# VestibularVR_H1-module_v_1_1.net
KiCad netlist of a schematic drawn in EAGLE
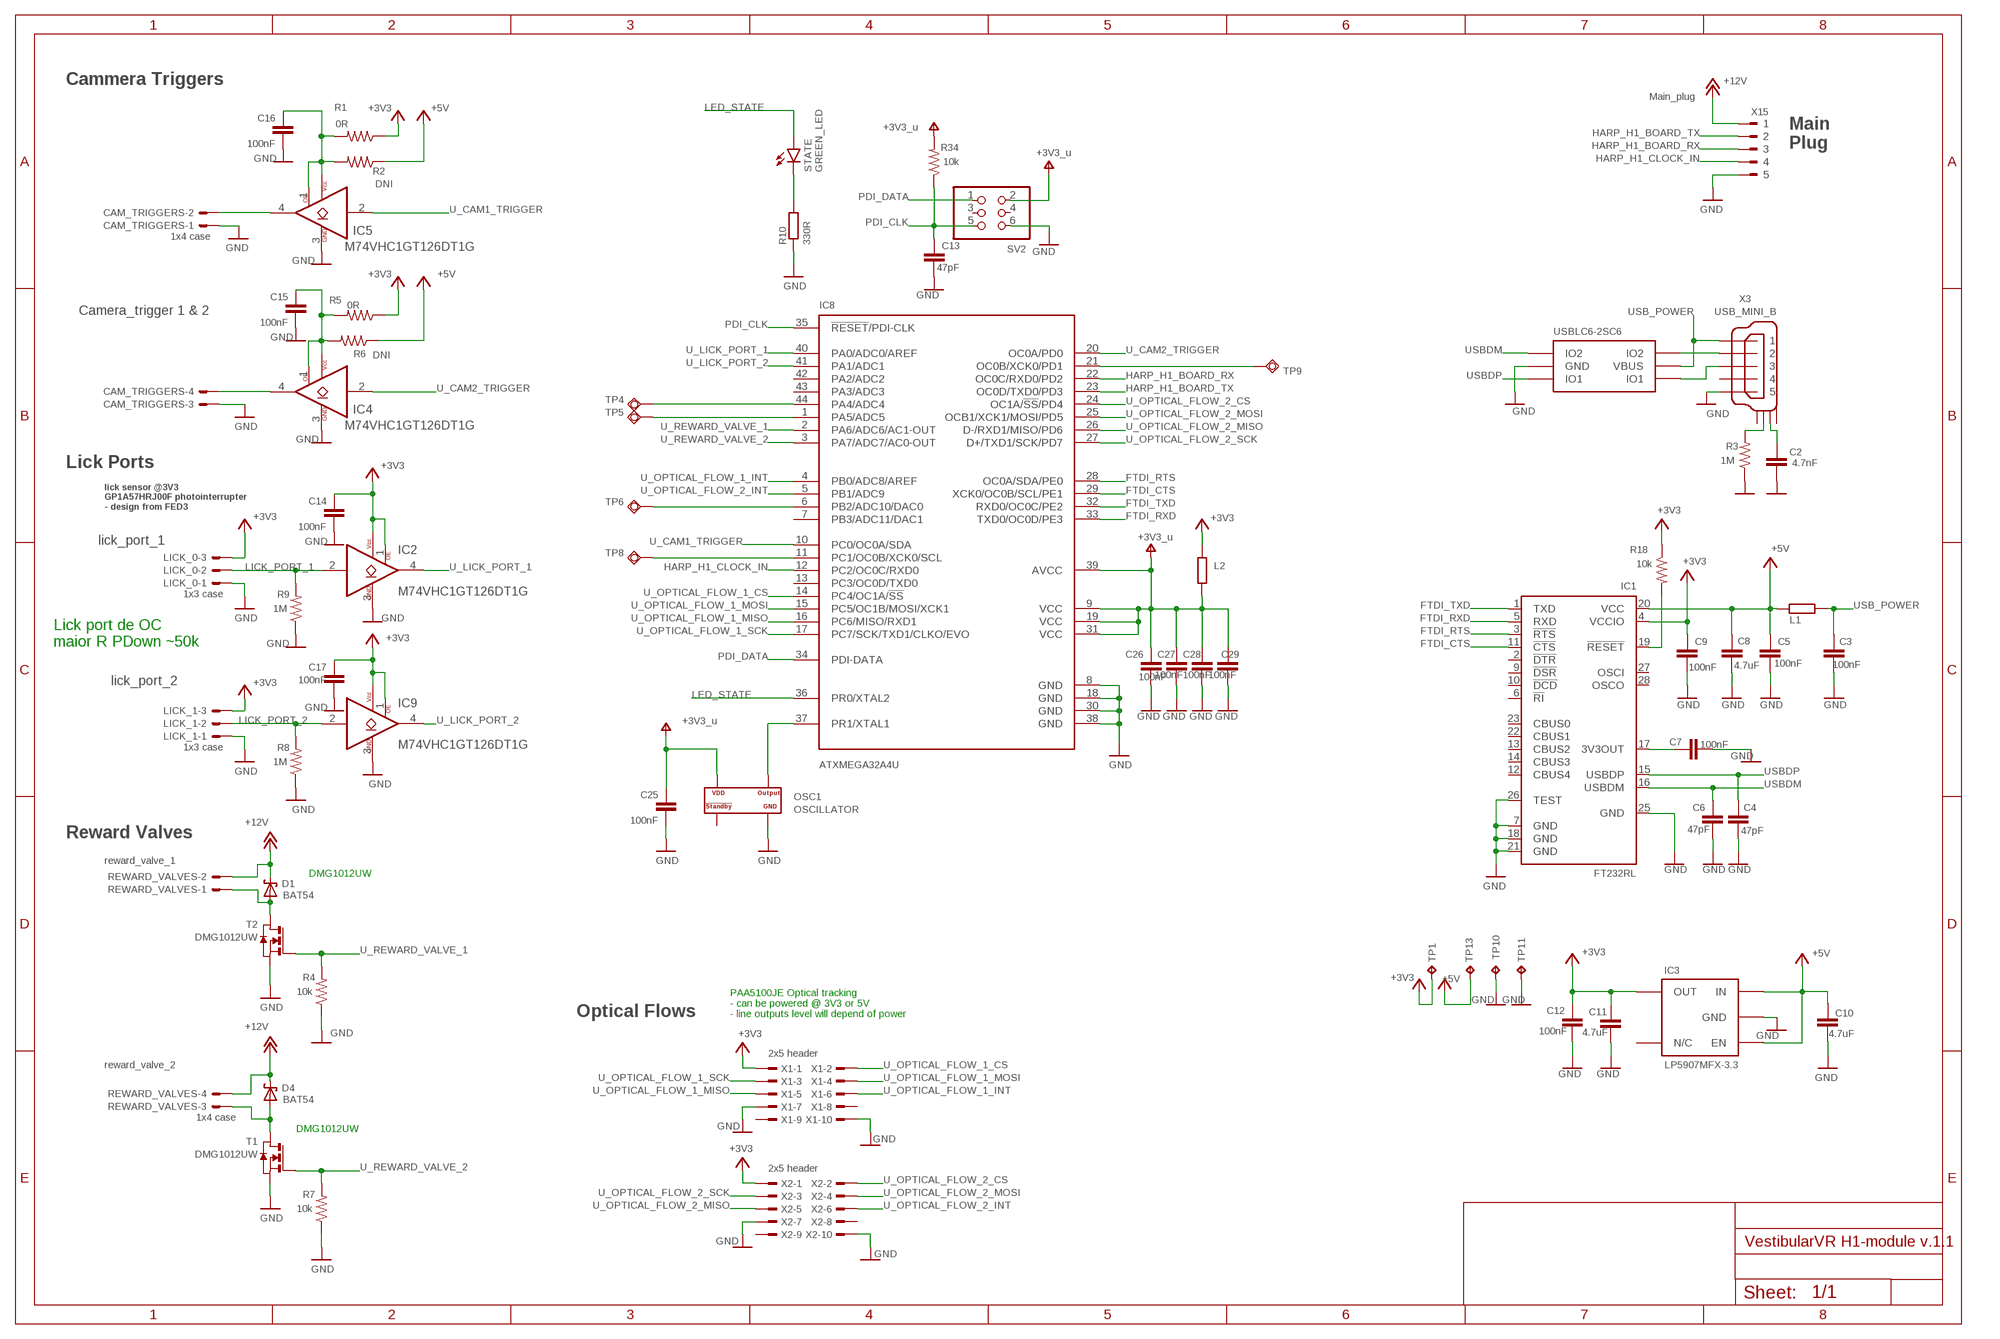
[diagram p0: schematic, sheet 1]

(export (version "E")
  (design (tool "Eeschema 10.0.6"))
  (components
    (comp (ref "C2")
      (value "4.7nF")
      (footprint "eagle-import:C0402K")
      (fields (field (name "MPN") "CC0402KRX7R8BB472"))
      (libsource (lib "eagle-import") (part "C-EUC0402K"))
    )
    (comp (ref "C3")
      (value "100nF")
      (footprint "eagle-import:C0402K")
      (fields (field (name "MPN") "C1005X7R1H104K050BB"))
      (libsource (lib "eagle-import") (part "C-EUC0402K"))
    )
    (comp (ref "C4")
      (value "47pF")
      (footprint "eagle-import:C0402K")
      (fields (field (name "MPN") "04025A470JAT2A"))
      (libsource (lib "eagle-import") (part "C-EUC0402K"))
    )
    (comp (ref "C5")
      (value "100nF")
      (footprint "eagle-import:C0402K")
      (fields (field (name "MPN") "C1005X7R1H104K050BB"))
      (libsource (lib "eagle-import") (part "C-EUC0402K"))
    )
    (comp (ref "C6")
      (value "47pF")
      (footprint "eagle-import:C0402K")
      (fields (field (name "MPN") "04025A470JAT2A"))
      (libsource (lib "eagle-import") (part "C-EUC0402K"))
    )
    (comp (ref "C7")
      (value "100nF")
      (footprint "eagle-import:C0402K")
      (fields (field (name "MPN") "C1005X7R1H104K050BB"))
      (libsource (lib "eagle-import") (part "C-EUC0402K"))
    )
    (comp (ref "C8")
      (value "4.7uF")
      (footprint "eagle-import:C0603")
      (fields (field (name "MPN") "C1608X6S1C475K080AC"))
      (libsource (lib "eagle-import") (part "C-EUC0603"))
    )
    (comp (ref "C9")
      (value "100nF")
      (footprint "eagle-import:C0402K")
      (fields (field (name "MPN") "C1005X7R1H104K050BB"))
      (libsource (lib "eagle-import") (part "C-EUC0402K"))
    )
    (comp (ref "C10")
      (value "4.7uF")
      (footprint "eagle-import:C0603K")
      (fields (field (name "MPN") "C1608X6S1C475K080AC"))
      (libsource (lib "eagle-import") (part "C-EUC0603K"))
    )
    (comp (ref "C11")
      (value "4.7uF")
      (footprint "eagle-import:C0603K")
      (fields (field (name "MPN") "C1608X6S1C475K080AC"))
      (libsource (lib "eagle-import") (part "C-EUC0603K"))
    )
    (comp (ref "C12")
      (value "100nF")
      (footprint "eagle-import:C0402K")
      (fields (field (name "MPN") "C1005X7R1H104K050BB"))
      (libsource (lib "eagle-import") (part "C-EUC0402K"))
    )
    (comp (ref "C13")
      (value "47pF")
      (footprint "eagle-import:C0402K")
      (fields (field (name "MPN") "04025A470JAT2A"))
      (libsource (lib "eagle-import") (part "C-EUC0402K"))
    )
    (comp (ref "C14")
      (value "100nF")
      (footprint "eagle-import:C0402K")
      (fields (field (name "MPN") "C1005X7R1H104K050BB"))
      (libsource (lib "eagle-import") (part "C-EUC0402K"))
    )
    (comp (ref "C15")
      (value "100nF")
      (footprint "eagle-import:C0402K")
      (fields (field (name "MPN") "C1005X7R1H104K050BB"))
      (libsource (lib "eagle-import") (part "C-EUC0402K"))
    )
    (comp (ref "C16")
      (value "100nF")
      (footprint "eagle-import:C0402K")
      (fields (field (name "MPN") "C1005X7R1H104K050BB"))
      (libsource (lib "eagle-import") (part "C-EUC0402K"))
    )
    (comp (ref "C17")
      (value "100nF")
      (footprint "eagle-import:C0402K")
      (fields (field (name "MPN") "C1005X7R1H104K050BB"))
      (libsource (lib "eagle-import") (part "C-EUC0402K"))
    )
    (comp (ref "C25")
      (value "100nF")
      (footprint "eagle-import:C0402K")
      (fields (field (name "MPN") "C1005X7R1H104K050BB"))
      (libsource (lib "eagle-import") (part "C-EUC0402K"))
    )
    (comp (ref "C26")
      (value "100nF")
      (footprint "eagle-import:C0402K")
      (fields (field (name "MPN") "C1005X7R1H104K050BB"))
      (libsource (lib "eagle-import") (part "C-EUC0402K"))
    )
    (comp (ref "C27")
      (value "100nF")
      (footprint "eagle-import:C0402K")
      (fields (field (name "MPN") "C1005X7R1H104K050BB"))
      (libsource (lib "eagle-import") (part "C-EUC0402K"))
    )
    (comp (ref "C28")
      (value "100nF")
      (footprint "eagle-import:C0402K")
      (fields (field (name "MPN") "C1005X7R1H104K050BB"))
      (libsource (lib "eagle-import") (part "C-EUC0402K"))
    )
    (comp (ref "C29")
      (value "100nF")
      (footprint "eagle-import:C0402K")
      (fields (field (name "MPN") "C1005X7R1H104K050BB"))
      (libsource (lib "eagle-import") (part "C-EUC0402K"))
    )
    (comp (ref "CAM_TRIGGERS")
      (value "1x4 case")
      (footprint "eagle-import:22-23-2041")
      (fields
        (field (name "MF") "MOLEX")
        (field (name "MPN") "22-23-2041")
        (field (name "MF_1") "-")
        (field (name "MPN_1") "282834-4")
        (field (name "OEPS") "OEPS070036")
      )
      (libsource (lib "eagle-import") (part "22-23-2041"))
    )
    (comp (ref "D1")
      (value "BAT54")
      (footprint "eagle-import:SOT23")
      (fields (field (name "MPN") "BAT54SLT1G"))
      (libsource (lib "eagle-import") (part "BAT54"))
    )
    (comp (ref "D4")
      (value "BAT54")
      (footprint "eagle-import:SOT23")
      (fields (field (name "MPN") "BAT54SLT1G"))
      (libsource (lib "eagle-import") (part "BAT54"))
    )
    (comp (ref "IC1")
      (value "FT232RL")
      (footprint "eagle-import:SSOP28")
      (libsource (lib "eagle-import") (part "FT232RL"))
    )
    (comp (ref "IC2")
      (value "M74VHC1GT126DT1G")
      (footprint "eagle-import:TSOP-5")
      (libsource (lib "eagle-import") (part "M74VHC1GT126DT1G"))
    )
    (comp (ref "IC3")
      (value "LP5907MFX-3.3")
      (footprint "eagle-import:TSOT23-5")
      (fields (field (name "MPN") "LP5907MFX-3.3/NOPB"))
      (libsource (lib "eagle-import") (part "TLV700XX"))
    )
    (comp (ref "IC4")
      (value "M74VHC1GT126DT1G")
      (footprint "eagle-import:TSOP-5")
      (libsource (lib "eagle-import") (part "M74VHC1GT126DT1G"))
    )
    (comp (ref "IC5")
      (value "M74VHC1GT126DT1G")
      (footprint "eagle-import:TSOP-5")
      (libsource (lib "eagle-import") (part "M74VHC1GT126DT1G"))
    )
    (comp (ref "IC7")
      (value "USBLC6-2SC6")
      (footprint "eagle-import:SOT23-6L")
      (libsource (lib "eagle-import") (part "USBLC6-2SC6"))
    )
    (comp (ref "IC8")
      (value "ATXMEGA32A4U")
      (footprint "eagle-import:TQFP44")
      (fields (field (name "MPN") "ATXMEGA32A4U-AUR"))
      (libsource (lib "eagle-import") (part "XMEGA-A4_AT-XMEGA-XXA4-AUTQFP44"))
    )
    (comp (ref "IC9")
      (value "M74VHC1GT126DT1G")
      (footprint "eagle-import:TSOP-5")
      (libsource (lib "eagle-import") (part "M74VHC1GT126DT1G"))
    )
    (comp (ref "L1")
      (value "40R@100MHz")
      (footprint "eagle-import:R0603")
      (fields (field (name "MPN") "MI0805K400R-10"))
      (libsource (lib "eagle-import") (part "R-EU_R0603"))
    )
    (comp (ref "L2")
      (value "40R@100MHz")
      (footprint "eagle-import:R0603")
      (fields (field (name "MPN") "MI0805K400R-10"))
      (libsource (lib "eagle-import") (part "R-EU_R0603"))
    )
    (comp (ref "LICK_0")
      (value "1x3 case")
      (footprint "eagle-import:22-23-2031")
      (fields
        (field (name "MF") "MOLEX")
        (field (name "MPN") "22-23-2031")
        (field (name "MF_1") "-")
        (field (name "MPN_1") "282834-3")
        (field (name "OEPS") "OEPS070035")
      )
      (libsource (lib "eagle-import") (part "22-23-2031"))
    )
    (comp (ref "LICK_1")
      (value "1x3 case")
      (footprint "eagle-import:22-23-2031")
      (fields
        (field (name "MF") "MOLEX")
        (field (name "MPN") "22-23-2031")
        (field (name "MF_1") "-")
        (field (name "MPN_1") "282834-3")
        (field (name "OEPS") "OEPS070035")
      )
      (libsource (lib "eagle-import") (part "22-23-2031"))
    )
    (comp (ref "OSC1")
      (value "OSCILLATOR")
      (footprint "eagle-import:OSCILLATOR_3.2X2.5")
      (fields (field (name "MPN") "DSC1001CI5-032.0000"))
      (libsource (lib "eagle-import") (part "OSCILLATOR"))
    )
    (comp (ref "R1")
      (value "0R")
      (footprint "eagle-import:R0402@1")
      (fields (field (name "MPN") "RC0402JR-070RL"))
      (libsource (lib "eagle-import") (part "R-US_R0402"))
    )
    (comp (ref "R2")
      (value "DNI")
      (footprint "eagle-import:R0402@1")
      (libsource (lib "eagle-import") (part "R-US_R0402"))
    )
    (comp (ref "R3")
      (value "1M")
      (footprint "eagle-import:R0402@1")
      (fields (field (name "MPN") "CRCW04021M00FKED"))
      (libsource (lib "eagle-import") (part "R-US_R0402"))
    )
    (comp (ref "R4")
      (value "10k")
      (footprint "eagle-import:R0402@1")
      (fields (field (name "MPN") "CRCW040210K0FKED"))
      (libsource (lib "eagle-import") (part "R-US_R0402"))
    )
    (comp (ref "R5")
      (value "0R")
      (footprint "eagle-import:R0402@1")
      (fields (field (name "MPN") "RC0402JR-070RL"))
      (libsource (lib "eagle-import") (part "R-US_R0402"))
    )
    (comp (ref "R6")
      (value "DNI")
      (footprint "eagle-import:R0402@1")
      (libsource (lib "eagle-import") (part "R-US_R0402"))
    )
    (comp (ref "R7")
      (value "10k")
      (footprint "eagle-import:R0402@1")
      (fields (field (name "MPN") "CRCW040210K0FKED"))
      (libsource (lib "eagle-import") (part "R-US_R0402"))
    )
    (comp (ref "R8")
      (value "1M")
      (footprint "eagle-import:R0402@1")
      (fields (field (name "MPN") "CRCW04021M00FKED"))
      (libsource (lib "eagle-import") (part "R-US_R0402"))
    )
    (comp (ref "R9")
      (value "1M")
      (footprint "eagle-import:R0402@1")
      (fields (field (name "MPN") "CRCW04021M00FKED"))
      (libsource (lib "eagle-import") (part "R-US_R0402"))
    )
    (comp (ref "R10")
      (value "330R")
      (footprint "eagle-import:R0402")
      (fields (field (name "MPN") "RC0402FR-07330RL"))
      (libsource (lib "eagle-import") (part "R-EU_R0402"))
    )
    (comp (ref "R18")
      (value "10k")
      (footprint "eagle-import:R0402@1")
      (fields (field (name "MPN") "CRCW040210K0FKED"))
      (libsource (lib "eagle-import") (part "R-US_R0402"))
    )
    (comp (ref "R34")
      (value "10k")
      (footprint "eagle-import:R0402@1")
      (fields (field (name "MPN") "CRCW040210K0FKED"))
      (libsource (lib "eagle-import") (part "R-US_R0402"))
    )
    (comp (ref "REWARD_VALVES")
      (value "1x4 case")
      (footprint "eagle-import:22-23-2041")
      (fields
        (field (name "MF") "MOLEX")
        (field (name "MPN") "22-23-2041")
        (field (name "MF_1") "-")
        (field (name "MPN_1") "282834-4")
        (field (name "OEPS") "OEPS070036")
      )
      (libsource (lib "eagle-import") (part "22-23-2041"))
    )
    (comp (ref "STATE")
      (value "GREEN_LED")
      (footprint "eagle-import:CHIP-LED0603")
      (fields (field (name "MPN") "LTST-C191KGKT"))
      (libsource (lib "eagle-import") (part "LEDCHIP-LED0603"))
    )
    (comp (ref "SV2")
      (value "PINHD-2X3")
      (footprint "eagle-import:2X03")
      (fields (field (name "MPN") "609-3210-ND"))
      (libsource (lib "eagle-import") (part "PINHD-2X3"))
    )
    (comp (ref "T1")
      (value "DMG1012UW")
      (footprint "eagle-import:SOT323")
      (fields (field (name "MPN") "DMG1012UW-7"))
      (libsource (lib "eagle-import") (part "DMG1012UW-7"))
    )
    (comp (ref "T2")
      (value "DMG1012UW")
      (footprint "eagle-import:SOT323")
      (fields (field (name "MPN") "DMG1012UW-7"))
      (libsource (lib "eagle-import") (part "DMG1012UW-7"))
    )
    (comp (ref "TP1")
      (value "NO_COMPONENT")
      (footprint "eagle-import:B1,27")
      (libsource (lib "eagle-import") (part "TPB1,27"))
    )
    (comp (ref "TP4")
      (value "NO_COMPONENT")
      (footprint "eagle-import:TP11R")
      (libsource (lib "eagle-import") (part "TPSQTP11R"))
    )
    (comp (ref "TP5")
      (value "NO_COMPONENT")
      (footprint "eagle-import:TP11R")
      (libsource (lib "eagle-import") (part "TPSQTP11R"))
    )
    (comp (ref "TP6")
      (value "NO_COMPONENT")
      (footprint "eagle-import:TP11R")
      (libsource (lib "eagle-import") (part "TPSQTP11R"))
    )
    (comp (ref "TP8")
      (value "NO_COMPONENT")
      (footprint "eagle-import:TP11R")
      (libsource (lib "eagle-import") (part "TPSQTP11R"))
    )
    (comp (ref "TP9")
      (value "NO_COMPONENT")
      (footprint "eagle-import:TP11R")
      (libsource (lib "eagle-import") (part "TPSQTP11R"))
    )
    (comp (ref "TP10")
      (value "NO_COMPONENT")
      (footprint "eagle-import:B1,27")
      (libsource (lib "eagle-import") (part "TPB1,27"))
    )
    (comp (ref "TP11")
      (value "NO_COMPONENT")
      (footprint "eagle-import:B1,27")
      (libsource (lib "eagle-import") (part "TPB1,27"))
    )
    (comp (ref "TP13")
      (value "NO_COMPONENT")
      (footprint "eagle-import:B1,27")
      (libsource (lib "eagle-import") (part "TPB1,27"))
    )
    (comp (ref "X1")
      (value "2x5 header")
      (footprint "eagle-import:TSW-105-02-S-D")
      (fields (field (name "MPN") "2x5 header") (field (name "OEPS") "n.a."))
      (libsource (lib "eagle-import") (part "TSW-105-02-S-D"))
    )
    (comp (ref "X2")
      (value "2x5 header")
      (footprint "eagle-import:TSW-105-02-S-D")
      (fields (field (name "MPN") "2x5 header") (field (name "OEPS") "n.a."))
      (libsource (lib "eagle-import") (part "TSW-105-02-S-D"))
    )
    (comp (ref "X3")
      (value "USB_MINI_B")
      (footprint "eagle-import:240-0002-1")
      (fields (field (name "MPN") "UX60-MB-5S8"))
      (libsource (lib "eagle-import") (part "USB_MINI_B"))
    )
    (comp (ref "X15")
      (value "Main_plug")
      (footprint "eagle-import:90G-5")
      (fields (field (name "MPN") "20.155MH/5-E"))
      (libsource (lib "eagle-import") (part "90G-5"))
    )
  )
  (nets
    (net (code "1") (name "+3V3") (class "Default")
      (node (ref "C11") (pin "1") (pinfunction "1_1") (pintype "passive"))
      (node (ref "C12") (pin "1") (pinfunction "1_1") (pintype "passive"))
      (node (ref "C14") (pin "1") (pinfunction "1_1") (pintype "passive"))
      (node (ref "C17") (pin "1") (pinfunction "1_1") (pintype "passive"))
      (node (ref "C9") (pin "1") (pinfunction "1_1") (pintype "passive"))
      (node (ref "IC1") (pin "4") (pinfunction "VCCIO_4") (pintype "power_in"))
      (node (ref "IC2") (pin "1") (pinfunction "OE_1") (pintype "bidirectional"))
      (node (ref "IC2") (pin "5") (pinfunction "VCC_5") (pintype "bidirectional"))
      (node (ref "IC3") (pin "5") (pinfunction "OUT_5") (pintype "bidirectional"))
      (node (ref "IC9") (pin "1") (pinfunction "OE_1") (pintype "bidirectional"))
      (node (ref "IC9") (pin "5") (pinfunction "VCC_5") (pintype "bidirectional"))
      (node (ref "L2") (pin "2") (pinfunction "2_2") (pintype "passive"))
      (node (ref "LICK_0") (pin "3") (pinfunction "S_3") (pintype "passive"))
      (node (ref "LICK_1") (pin "3") (pinfunction "S_3") (pintype "passive"))
      (node (ref "R1") (pin "1") (pinfunction "1_1") (pintype "passive"))
      (node (ref "R18") (pin "1") (pinfunction "1_1") (pintype "passive"))
      (node (ref "R5") (pin "1") (pinfunction "1_1") (pintype "passive"))
      (node (ref "TP1") (pin "TP") (pinfunction "TP_TP") (pintype "input"))
      (node (ref "X1") (pin "1") (pinfunction "1_1") (pintype "passive"))
      (node (ref "X2") (pin "1") (pinfunction "1_1") (pintype "passive"))
    )
    (net (code "2") (name "+3V3_u") (class "Default")
      (node (ref "C25") (pin "1") (pinfunction "1_1") (pintype "passive"))
      (node (ref "C26") (pin "1") (pinfunction "1_1") (pintype "passive"))
      (node (ref "C27") (pin "1") (pinfunction "1_1") (pintype "passive"))
      (node (ref "C28") (pin "1") (pinfunction "1_1") (pintype "passive"))
      (node (ref "C29") (pin "1") (pinfunction "1_1") (pintype "passive"))
      (node (ref "IC8") (pin "19") (pinfunction "VCC_19") (pintype "power_in"))
      (node (ref "IC8") (pin "31") (pinfunction "VCC_31") (pintype "power_in"))
      (node (ref "IC8") (pin "39") (pinfunction "AVCC_39") (pintype "power_in"))
      (node (ref "IC8") (pin "9") (pinfunction "VCC_9") (pintype "power_in"))
      (node (ref "L2") (pin "1") (pinfunction "1_1") (pintype "passive"))
      (node (ref "OSC1") (pin "P$4") (pinfunction "VDD_P$4") (pintype "passive"))
      (node (ref "R34") (pin "2") (pinfunction "2_2") (pintype "passive"))
      (node (ref "SV2") (pin "2") (pinfunction "2_2") (pintype "passive"))
    )
    (net (code "3") (name "+5V") (class "Default")
      (node (ref "C10") (pin "1") (pinfunction "1_1") (pintype "passive"))
      (node (ref "C5") (pin "1") (pinfunction "1_1") (pintype "passive"))
      (node (ref "C8") (pin "1") (pinfunction "1_1") (pintype "passive"))
      (node (ref "IC1") (pin "20") (pinfunction "VCC_20") (pintype "power_in"))
      (node (ref "IC3") (pin "1") (pinfunction "IN_1") (pintype "bidirectional"))
      (node (ref "IC3") (pin "3") (pinfunction "EN_3") (pintype "bidirectional"))
      (node (ref "L1") (pin "1") (pinfunction "1_1") (pintype "passive"))
      (node (ref "R2") (pin "1") (pinfunction "1_1") (pintype "passive"))
      (node (ref "R6") (pin "1") (pinfunction "1_1") (pintype "passive"))
      (node (ref "TP13") (pin "TP") (pinfunction "TP_TP") (pintype "input"))
    )
    (net (code "4") (name "+12V") (class "Default")
      (node (ref "D1") (pin "3") (pinfunction "C_3") (pintype "passive"))
      (node (ref "D4") (pin "3") (pinfunction "C_3") (pintype "passive"))
      (node (ref "REWARD_VALVES") (pin "2") (pinfunction "S_2") (pintype "passive"))
      (node (ref "REWARD_VALVES") (pin "4") (pinfunction "S_4") (pintype "passive"))
      (node (ref "X15") (pin "1") (pinfunction "1_1") (pintype "passive"))
    )
    (net (code "5") (name "/FTDI_CTS") (class "Default")
      (node (ref "IC1") (pin "11") (pinfunction "~{CTS}_11") (pintype "input"))
      (node (ref "IC8") (pin "29") (pinfunction "XCK0/OC0B/SCL/PE1_29") (pintype "bidirectional"))
    )
    (net (code "6") (name "/FTDI_RTS") (class "Default")
      (node (ref "IC1") (pin "3") (pinfunction "~{RTS}_3") (pintype "output"))
      (node (ref "IC8") (pin "28") (pinfunction "OC0A/SDA/PE0_28") (pintype "bidirectional"))
    )
    (net (code "7") (name "/FTDI_RXD") (class "Default")
      (node (ref "IC1") (pin "5") (pinfunction "RXD_5") (pintype "input"))
      (node (ref "IC8") (pin "33") (pinfunction "TXD0/OC0D/PE3_33") (pintype "bidirectional"))
    )
    (net (code "8") (name "/FTDI_TXD") (class "Default")
      (node (ref "IC1") (pin "1") (pinfunction "TXD_1") (pintype "output"))
      (node (ref "IC8") (pin "32") (pinfunction "RXD0/OC0C/PE2_32") (pintype "bidirectional"))
    )
    (net (code "9") (name "/HARP_H1_BOARD_RX") (class "Default")
      (node (ref "IC8") (pin "22") (pinfunction "OC0C/RXD0/PD2_22") (pintype "bidirectional"))
      (node (ref "X15") (pin "3") (pinfunction "3_3") (pintype "passive"))
    )
    (net (code "10") (name "/HARP_H1_BOARD_TX") (class "Default")
      (node (ref "IC8") (pin "23") (pinfunction "OC0D/TXD0/PD3_23") (pintype "bidirectional"))
      (node (ref "X15") (pin "2") (pinfunction "2_2") (pintype "passive"))
    )
    (net (code "11") (name "/HARP_H1_CLOCK_IN") (class "Default")
      (node (ref "IC8") (pin "12") (pinfunction "PC2/OC0C/RXD0_12") (pintype "bidirectional"))
      (node (ref "X15") (pin "4") (pinfunction "4_4") (pintype "passive"))
    )
    (net (code "12") (name "/LED_STATE") (class "Default")
      (node (ref "IC8") (pin "36") (pinfunction "PR0/XTAL2_36") (pintype "bidirectional"))
      (node (ref "STATE") (pin "A") (pinfunction "A_A") (pintype "passive"))
    )
    (net (code "13") (name "/LICK_PORT_1") (class "Default")
      (node (ref "IC2") (pin "2") (pinfunction "A_2") (pintype "bidirectional"))
      (node (ref "LICK_0") (pin "2") (pinfunction "S_2") (pintype "passive"))
      (node (ref "R9") (pin "2") (pinfunction "2_2") (pintype "passive"))
    )
    (net (code "14") (name "/LICK_PORT_2") (class "Default")
      (node (ref "IC9") (pin "2") (pinfunction "A_2") (pintype "bidirectional"))
      (node (ref "LICK_1") (pin "2") (pinfunction "S_2") (pintype "passive"))
      (node (ref "R8") (pin "2") (pinfunction "2_2") (pintype "passive"))
    )
    (net (code "15") (name "/PDI_CLK") (class "Default")
      (node (ref "C13") (pin "1") (pinfunction "1_1") (pintype "passive"))
      (node (ref "IC8") (pin "35") (pinfunction "~{RESET}/PDI-CLK_35") (pintype "input"))
      (node (ref "R34") (pin "1") (pinfunction "1_1") (pintype "passive"))
      (node (ref "SV2") (pin "5") (pinfunction "5_5") (pintype "passive"))
    )
    (net (code "16") (name "/PDI_DATA") (class "Default")
      (node (ref "IC8") (pin "34") (pinfunction "PDI-DATA_34") (pintype "bidirectional"))
      (node (ref "SV2") (pin "1") (pinfunction "1_1") (pintype "passive"))
    )
    (net (code "17") (name "/USBDM") (class "Default")
      (node (ref "C6") (pin "1") (pinfunction "1_1") (pintype "passive"))
      (node (ref "IC1") (pin "16") (pinfunction "USBDM_16") (pintype "bidirectional"))
      (node (ref "IC7") (pin "P$3") (pinfunction "IO2_P$3") (pintype "bidirectional"))
    )
    (net (code "18") (name "/USBDP") (class "Default")
      (node (ref "C4") (pin "1") (pinfunction "1_1") (pintype "passive"))
      (node (ref "IC1") (pin "15") (pinfunction "USBDP_15") (pintype "bidirectional"))
      (node (ref "IC7") (pin "P$1") (pinfunction "IO1_P$1") (pintype "bidirectional"))
    )
    (net (code "19") (name "/USB_POWER") (class "Default")
      (node (ref "C3") (pin "1") (pinfunction "1_1") (pintype "passive"))
      (node (ref "IC7") (pin "P$5") (pinfunction "VBUS_P$5") (pintype "bidirectional"))
      (node (ref "L1") (pin "2") (pinfunction "2_2") (pintype "passive"))
      (node (ref "X3") (pin "P$1") (pinfunction "1_P$1") (pintype "bidirectional"))
    )
    (net (code "20") (name "/U_CAM1_TRIGGER") (class "Default")
      (node (ref "IC5") (pin "2") (pinfunction "A_2") (pintype "bidirectional"))
      (node (ref "IC8") (pin "10") (pinfunction "PC0/OC0A/SDA_10") (pintype "bidirectional"))
    )
    (net (code "21") (name "/U_CAM2_TRIGGER") (class "Default")
      (node (ref "IC4") (pin "2") (pinfunction "A_2") (pintype "bidirectional"))
      (node (ref "IC8") (pin "20") (pinfunction "OC0A/PD0_20") (pintype "bidirectional"))
    )
    (net (code "22") (name "/U_LICK_PORT_1") (class "Default")
      (node (ref "IC2") (pin "4") (pinfunction "Y_4") (pintype "bidirectional"))
      (node (ref "IC8") (pin "40") (pinfunction "PA0/ADC0/AREF_40") (pintype "bidirectional"))
    )
    (net (code "23") (name "/U_LICK_PORT_2") (class "Default")
      (node (ref "IC8") (pin "41") (pinfunction "PA1/ADC1_41") (pintype "bidirectional"))
      (node (ref "IC9") (pin "4") (pinfunction "Y_4") (pintype "bidirectional"))
    )
    (net (code "24") (name "/U_OPTICAL_FLOW_1_CS") (class "Default")
      (node (ref "IC8") (pin "14") (pinfunction "PC4/OC1A/~{SS}_14") (pintype "bidirectional"))
      (node (ref "X1") (pin "2") (pinfunction "1_2") (pintype "passive"))
    )
    (net (code "25") (name "/U_OPTICAL_FLOW_1_INT") (class "Default")
      (node (ref "IC8") (pin "4") (pinfunction "PB0/ADC8/AREF_4") (pintype "bidirectional"))
      (node (ref "X1") (pin "6") (pinfunction "1_6") (pintype "passive"))
    )
    (net (code "26") (name "/U_OPTICAL_FLOW_1_MISO") (class "Default")
      (node (ref "IC8") (pin "16") (pinfunction "PC6/MISO/RXD1_16") (pintype "bidirectional"))
      (node (ref "X1") (pin "5") (pinfunction "1_5") (pintype "passive"))
    )
    (net (code "27") (name "/U_OPTICAL_FLOW_1_MOSI") (class "Default")
      (node (ref "IC8") (pin "15") (pinfunction "PC5/OC1B/MOSI/XCK1_15") (pintype "bidirectional"))
      (node (ref "X1") (pin "4") (pinfunction "1_4") (pintype "passive"))
    )
    (net (code "28") (name "/U_OPTICAL_FLOW_1_SCK") (class "Default")
      (node (ref "IC8") (pin "17") (pinfunction "PC7/SCK/TXD1/CLKO/EVO_17") (pintype "bidirectional"))
      (node (ref "X1") (pin "3") (pinfunction "1_3") (pintype "passive"))
    )
    (net (code "29") (name "/U_OPTICAL_FLOW_2_CS") (class "Default")
      (node (ref "IC8") (pin "24") (pinfunction "OC1A/~{SS}/PD4_24") (pintype "bidirectional"))
      (node (ref "X2") (pin "2") (pinfunction "1_2") (pintype "passive"))
    )
    (net (code "30") (name "/U_OPTICAL_FLOW_2_INT") (class "Default")
      (node (ref "IC8") (pin "5") (pinfunction "PB1/ADC9_5") (pintype "bidirectional"))
      (node (ref "X2") (pin "6") (pinfunction "1_6") (pintype "passive"))
    )
    (net (code "31") (name "/U_OPTICAL_FLOW_2_MISO") (class "Default")
      (node (ref "IC8") (pin "26") (pinfunction "D-/RXD1/MISO/PD6_26") (pintype "bidirectional"))
      (node (ref "X2") (pin "5") (pinfunction "1_5") (pintype "passive"))
    )
    (net (code "32") (name "/U_OPTICAL_FLOW_2_MOSI") (class "Default")
      (node (ref "IC8") (pin "25") (pinfunction "OCB1/XCK1/MOSI/PD5_25") (pintype "bidirectional"))
      (node (ref "X2") (pin "4") (pinfunction "1_4") (pintype "passive"))
    )
    (net (code "33") (name "/U_OPTICAL_FLOW_2_SCK") (class "Default")
      (node (ref "IC8") (pin "27") (pinfunction "D+/TXD1/SCK/PD7_27") (pintype "bidirectional"))
      (node (ref "X2") (pin "3") (pinfunction "1_3") (pintype "passive"))
    )
    (net (code "34") (name "/U_REWARD_VALVE_1") (class "Default")
      (node (ref "IC8") (pin "2") (pinfunction "PA6/ADC6/AC1-OUT_2") (pintype "bidirectional"))
      (node (ref "R4") (pin "2") (pinfunction "2_2") (pintype "passive"))
      (node (ref "T2") (pin "1") (pinfunction "G_1") (pintype "passive"))
    )
    (net (code "35") (name "/U_REWARD_VALVE_2") (class "Default")
      (node (ref "IC8") (pin "3") (pinfunction "PA7/ADC7/AC0-OUT_3") (pintype "bidirectional"))
      (node (ref "R7") (pin "2") (pinfunction "2_2") (pintype "passive"))
      (node (ref "T1") (pin "1") (pinfunction "G_1") (pintype "passive"))
    )
    (net (code "36") (name "GND") (class "Default")
      (node (ref "C10") (pin "2") (pinfunction "2_2") (pintype "passive"))
      (node (ref "C11") (pin "2") (pinfunction "2_2") (pintype "passive"))
      (node (ref "C12") (pin "2") (pinfunction "2_2") (pintype "passive"))
      (node (ref "C13") (pin "2") (pinfunction "2_2") (pintype "passive"))
      (node (ref "C14") (pin "2") (pinfunction "2_2") (pintype "passive"))
      (node (ref "C15") (pin "2") (pinfunction "2_2") (pintype "passive"))
      (node (ref "C16") (pin "2") (pinfunction "2_2") (pintype "passive"))
      (node (ref "C17") (pin "2") (pinfunction "2_2") (pintype "passive"))
      (node (ref "C2") (pin "2") (pinfunction "2_2") (pintype "passive"))
      (node (ref "C25") (pin "2") (pinfunction "2_2") (pintype "passive"))
      (node (ref "C26") (pin "2") (pinfunction "2_2") (pintype "passive"))
      (node (ref "C27") (pin "2") (pinfunction "2_2") (pintype "passive"))
      (node (ref "C28") (pin "2") (pinfunction "2_2") (pintype "passive"))
      (node (ref "C29") (pin "2") (pinfunction "2_2") (pintype "passive"))
      (node (ref "C3") (pin "2") (pinfunction "2_2") (pintype "passive"))
      (node (ref "C4") (pin "2") (pinfunction "2_2") (pintype "passive"))
      (node (ref "C5") (pin "2") (pinfunction "2_2") (pintype "passive"))
      (node (ref "C6") (pin "2") (pinfunction "2_2") (pintype "passive"))
      (node (ref "C7") (pin "2") (pinfunction "2_2") (pintype "passive"))
      (node (ref "C8") (pin "2") (pinfunction "2_2") (pintype "passive"))
      (node (ref "C9") (pin "2") (pinfunction "2_2") (pintype "passive"))
      (node (ref "CAM_TRIGGERS") (pin "1") (pinfunction "S_1") (pintype "passive"))
      (node (ref "CAM_TRIGGERS") (pin "3") (pinfunction "S_3") (pintype "passive"))
      (node (ref "IC1") (pin "18") (pinfunction "GND_18") (pintype "power_in"))
      (node (ref "IC1") (pin "21") (pinfunction "GND_21") (pintype "power_in"))
      (node (ref "IC1") (pin "25") (pinfunction "GND_25") (pintype "power_in"))
      (node (ref "IC1") (pin "26") (pinfunction "TEST_26") (pintype "input"))
      (node (ref "IC1") (pin "7") (pinfunction "GND_7") (pintype "power_in"))
      (node (ref "IC2") (pin "3") (pinfunction "GND_3") (pintype "bidirectional"))
      (node (ref "IC3") (pin "2") (pinfunction "GND_2") (pintype "bidirectional"))
      (node (ref "IC4") (pin "3") (pinfunction "GND_3") (pintype "bidirectional"))
      (node (ref "IC5") (pin "3") (pinfunction "GND_3") (pintype "bidirectional"))
      (node (ref "IC7") (pin "P$2") (pinfunction "GND_P$2") (pintype "bidirectional"))
      (node (ref "IC8") (pin "18") (pinfunction "GND_18") (pintype "power_in"))
      (node (ref "IC8") (pin "30") (pinfunction "GND_30") (pintype "power_in"))
      (node (ref "IC8") (pin "38") (pinfunction "GND_38") (pintype "power_in"))
      (node (ref "IC8") (pin "8") (pinfunction "GND_8") (pintype "power_in"))
      (node (ref "IC9") (pin "3") (pinfunction "GND_3") (pintype "bidirectional"))
      (node (ref "LICK_0") (pin "1") (pinfunction "S_1") (pintype "passive"))
      (node (ref "LICK_1") (pin "1") (pinfunction "S_1") (pintype "passive"))
      (node (ref "OSC1") (pin "P$2") (pinfunction "GND_P$2") (pintype "passive"))
      (node (ref "R10") (pin "1") (pinfunction "1_1") (pintype "passive"))
      (node (ref "R3") (pin "1") (pinfunction "1_1") (pintype "passive"))
      (node (ref "R4") (pin "1") (pinfunction "1_1") (pintype "passive"))
      (node (ref "R7") (pin "1") (pinfunction "1_1") (pintype "passive"))
      (node (ref "R8") (pin "1") (pinfunction "1_1") (pintype "passive"))
      (node (ref "R9") (pin "1") (pinfunction "1_1") (pintype "passive"))
      (node (ref "SV2") (pin "6") (pinfunction "6_6") (pintype "passive"))
      (node (ref "T1") (pin "2") (pinfunction "S_2") (pintype "passive"))
      (node (ref "T2") (pin "2") (pinfunction "S_2") (pintype "passive"))
      (node (ref "TP10") (pin "TP") (pinfunction "TP_TP") (pintype "input"))
      (node (ref "TP11") (pin "TP") (pinfunction "TP_TP") (pintype "input"))
      (node (ref "X1") (pin "10") (pinfunction "1_10") (pintype "passive"))
      (node (ref "X1") (pin "7") (pinfunction "1_7") (pintype "passive"))
      (node (ref "X15") (pin "5") (pinfunction "5_5") (pintype "passive"))
      (node (ref "X2") (pin "10") (pinfunction "1_10") (pintype "passive"))
      (node (ref "X2") (pin "7") (pinfunction "1_7") (pintype "passive"))
      (node (ref "X3") (pin "P$5") (pinfunction "5_P$5") (pintype "bidirectional"))
    )
    (net (code "37") (name "Net-(CAM_TRIGGERSB-S)") (class "Default")
      (node (ref "CAM_TRIGGERS") (pin "2") (pinfunction "S_2") (pintype "passive"))
      (node (ref "IC5") (pin "4") (pinfunction "Y_4") (pintype "bidirectional"))
    )
    (net (code "38") (name "Net-(CAM_TRIGGERSD-S)") (class "Default")
      (node (ref "CAM_TRIGGERS") (pin "4") (pinfunction "S_4") (pintype "passive"))
      (node (ref "IC4") (pin "4") (pinfunction "Y_4") (pintype "bidirectional"))
    )
    (net (code "39") (name "Net-(D1-A)") (class "Default")
      (node (ref "D1") (pin "1") (pinfunction "A_1") (pintype "passive"))
      (node (ref "REWARD_VALVES") (pin "1") (pinfunction "S_1") (pintype "passive"))
      (node (ref "T2") (pin "3") (pinfunction "D_3") (pintype "passive"))
    )
    (net (code "40") (name "Net-(D4-A)") (class "Default")
      (node (ref "D4") (pin "1") (pinfunction "A_1") (pintype "passive"))
      (node (ref "REWARD_VALVES") (pin "3") (pinfunction "S_3") (pintype "passive"))
      (node (ref "T1") (pin "3") (pinfunction "D_3") (pintype "passive"))
    )
    (net (code "41") (name "Net-(IC1-3V3OUT)") (class "Default")
      (node (ref "C7") (pin "1") (pinfunction "1_1") (pintype "passive"))
      (node (ref "IC1") (pin "17") (pinfunction "3V3OUT_17") (pintype "output"))
    )
    (net (code "42") (name "Net-(IC1-~{RESET})") (class "Default")
      (node (ref "IC1") (pin "19") (pinfunction "~{RESET}_19") (pintype "input"))
      (node (ref "R18") (pin "2") (pinfunction "2_2") (pintype "passive"))
    )
    (net (code "43") (name "Net-(IC4-OE)") (class "Default")
      (node (ref "C15") (pin "1") (pinfunction "1_1") (pintype "passive"))
      (node (ref "IC4") (pin "1") (pinfunction "OE_1") (pintype "bidirectional"))
      (node (ref "IC4") (pin "5") (pinfunction "VCC_5") (pintype "bidirectional"))
      (node (ref "R5") (pin "2") (pinfunction "2_2") (pintype "passive"))
      (node (ref "R6") (pin "2") (pinfunction "2_2") (pintype "passive"))
    )
    (net (code "44") (name "Net-(IC5-OE)") (class "Default")
      (node (ref "C16") (pin "1") (pinfunction "1_1") (pintype "passive"))
      (node (ref "IC5") (pin "1") (pinfunction "OE_1") (pintype "bidirectional"))
      (node (ref "IC5") (pin "5") (pinfunction "VCC_5") (pintype "bidirectional"))
      (node (ref "R1") (pin "2") (pinfunction "2_2") (pintype "passive"))
      (node (ref "R2") (pin "2") (pinfunction "2_2") (pintype "passive"))
    )
    (net (code "45") (name "Net-(IC8-OC0B{slash}XCK0{slash}PD1)") (class "Default")
      (node (ref "IC8") (pin "21") (pinfunction "OC0B/XCK0/PD1_21") (pintype "bidirectional"))
      (node (ref "TP9") (pin "TP") (pinfunction "TP_TP") (pintype "input"))
    )
    (net (code "46") (name "Net-(IC8-PA4{slash}ADC4)") (class "Default")
      (node (ref "IC8") (pin "44") (pinfunction "PA4/ADC4_44") (pintype "bidirectional"))
      (node (ref "TP4") (pin "TP") (pinfunction "TP_TP") (pintype "input"))
    )
    (net (code "47") (name "Net-(IC8-PA5{slash}ADC5)") (class "Default")
      (node (ref "IC8") (pin "1") (pinfunction "PA5/ADC5_1") (pintype "bidirectional"))
      (node (ref "TP5") (pin "TP") (pinfunction "TP_TP") (pintype "input"))
    )
    (net (code "48") (name "Net-(IC8-PB2{slash}ADC10{slash}DAC0)") (class "Default")
      (node (ref "IC8") (pin "6") (pinfunction "PB2/ADC10/DAC0_6") (pintype "bidirectional"))
      (node (ref "TP6") (pin "TP") (pinfunction "TP_TP") (pintype "input"))
    )
    (net (code "49") (name "Net-(IC8-PC1{slash}OC0B{slash}XCK0{slash}SCL)") (class "Default")
      (node (ref "IC8") (pin "11") (pinfunction "PC1/OC0B/XCK0/SCL_11") (pintype "bidirectional"))
      (node (ref "TP8") (pin "TP") (pinfunction "TP_TP") (pintype "input"))
    )
    (net (code "50") (name "Net-(IC8-PR1{slash}XTAL1)") (class "Default")
      (node (ref "IC8") (pin "37") (pinfunction "PR1/XTAL1_37") (pintype "bidirectional"))
      (node (ref "OSC1") (pin "P$3") (pinfunction "OUTPUT_P$3") (pintype "passive"))
    )
    (net (code "51") (name "Net-(R10-Pad2)") (class "Default")
      (node (ref "R10") (pin "2") (pinfunction "2_2") (pintype "passive"))
      (node (ref "STATE") (pin "C") (pinfunction "C_C") (pintype "passive"))
    )
    (net (code "52") (name "Net-(X3-2)") (class "Default")
      (node (ref "IC7") (pin "P$4") (pinfunction "IO2_P$4") (pintype "bidirectional"))
      (node (ref "X3") (pin "P$2") (pinfunction "2_P$2") (pintype "bidirectional"))
    )
    (net (code "53") (name "Net-(X3-3)") (class "Default")
      (node (ref "IC7") (pin "P$6") (pinfunction "IO1_P$6") (pintype "bidirectional"))
      (node (ref "X3") (pin "P$3") (pinfunction "3_P$3") (pintype "bidirectional"))
    )
    (net (code "54") (name "Net-(X3-P$2)") (class "Default")
      (node (ref "R3") (pin "2") (pinfunction "2_2") (pintype "passive"))
      (node (ref "X3") (pin "SHIELD_2") (pinfunction "P$2_SHIELD_2") (pintype "bidirectional"))
    )
    (net (code "55") (name "Net-(X3-P$3)") (class "Default")
      (node (ref "C2") (pin "1") (pinfunction "1_1") (pintype "passive"))
      (node (ref "X3") (pin "SHIELD_3") (pinfunction "P$3_SHIELD_3") (pintype "bidirectional"))
    )
    (net (code "56") (name "unconnected-(IC1-CBUS0-Pad23)") (class "Default")
      (node (ref "IC1") (pin "23") (pinfunction "CBUS0_23") (pintype "bidirectional"))
    )
    (net (code "57") (name "unconnected-(IC1-CBUS1-Pad22)") (class "Default")
      (node (ref "IC1") (pin "22") (pinfunction "CBUS1_22") (pintype "bidirectional"))
    )
    (net (code "58") (name "unconnected-(IC1-CBUS2-Pad13)") (class "Default")
      (node (ref "IC1") (pin "13") (pinfunction "CBUS2_13") (pintype "bidirectional"))
    )
    (net (code "59") (name "unconnected-(IC1-CBUS3-Pad14)") (class "Default")
      (node (ref "IC1") (pin "14") (pinfunction "CBUS3_14") (pintype "bidirectional"))
    )
    (net (code "60") (name "unconnected-(IC1-CBUS4-Pad12)") (class "Default")
      (node (ref "IC1") (pin "12") (pinfunction "CBUS4_12") (pintype "bidirectional"))
    )
    (net (code "61") (name "unconnected-(IC1-OSCI-Pad27)") (class "Default")
      (node (ref "IC1") (pin "27") (pinfunction "OSCI_27") (pintype "input"))
    )
    (net (code "62") (name "unconnected-(IC1-OSCO-Pad28)") (class "Default")
      (node (ref "IC1") (pin "28") (pinfunction "OSCO_28") (pintype "output"))
    )
    (net (code "63") (name "unconnected-(IC1-~{DCD}-Pad10)") (class "Default")
      (node (ref "IC1") (pin "10") (pinfunction "~{DCD}_10") (pintype "input"))
    )
    (net (code "64") (name "unconnected-(IC1-~{DSR}-Pad9)") (class "Default")
      (node (ref "IC1") (pin "9") (pinfunction "~{DSR}_9") (pintype "input"))
    )
    (net (code "65") (name "unconnected-(IC1-~{DTR}-Pad2)") (class "Default")
      (node (ref "IC1") (pin "2") (pinfunction "~{DTR}_2") (pintype "output"))
    )
    (net (code "66") (name "unconnected-(IC1-~{RI}-Pad6)") (class "Default")
      (node (ref "IC1") (pin "6") (pinfunction "~{RI}_6") (pintype "input"))
    )
    (net (code "67") (name "unconnected-(IC3-N{slash}C-Pad4)") (class "Default")
      (node (ref "IC3") (pin "4") (pinfunction "N/C_4") (pintype "bidirectional"))
    )
    (net (code "68") (name "unconnected-(IC8-PA2{slash}ADC2-Pad42)") (class "Default")
      (node (ref "IC8") (pin "42") (pinfunction "PA2/ADC2_42") (pintype "bidirectional"))
    )
    (net (code "69") (name "unconnected-(IC8-PA3{slash}ADC3-Pad43)") (class "Default")
      (node (ref "IC8") (pin "43") (pinfunction "PA3/ADC3_43") (pintype "bidirectional"))
    )
    (net (code "70") (name "unconnected-(IC8-PB3{slash}ADC11{slash}DAC1-Pad7)") (class "Default")
      (node (ref "IC8") (pin "7") (pinfunction "PB3/ADC11/DAC1_7") (pintype "bidirectional"))
    )
    (net (code "71") (name "unconnected-(IC8-PC3{slash}OC0D{slash}TXD0-Pad13)") (class "Default")
      (node (ref "IC8") (pin "13") (pinfunction "PC3/OC0D/TXD0_13") (pintype "bidirectional"))
    )
    (net (code "72") (name "unconnected-(OSC1-STANDBY#-PadP$1)") (class "Default")
      (node (ref "OSC1") (pin "P$1") (pinfunction "STANDBY#_P$1") (pintype "passive"))
    )
    (net (code "73") (name "unconnected-(SV2-Pad3)") (class "Default")
      (node (ref "SV2") (pin "3") (pinfunction "3_3") (pintype "passive"))
    )
    (net (code "74") (name "unconnected-(SV2-Pad4)") (class "Default")
      (node (ref "SV2") (pin "4") (pinfunction "4_4") (pintype "passive"))
    )
    (net (code "75") (name "unconnected-(X1I-1-Pad8)") (class "Default")
      (node (ref "X1") (pin "8") (pinfunction "1_8") (pintype "passive"))
    )
    (net (code "76") (name "unconnected-(X1J-1-Pad9)") (class "Default")
      (node (ref "X1") (pin "9") (pinfunction "1_9") (pintype "passive"))
    )
    (net (code "77") (name "unconnected-(X2I-1-Pad8)") (class "Default")
      (node (ref "X2") (pin "8") (pinfunction "1_8") (pintype "passive"))
    )
    (net (code "78") (name "unconnected-(X2J-1-Pad9)") (class "Default")
      (node (ref "X2") (pin "9") (pinfunction "1_9") (pintype "passive"))
    )
    (net (code "79") (name "unconnected-(X3-4-PadP$4)") (class "Default")
      (node (ref "X3") (pin "P$4") (pinfunction "4_P$4") (pintype "bidirectional"))
    )
    (net (code "80") (name "unconnected-(X3-P$1-PadSHIELD_1)") (class "Default")
      (node (ref "X3") (pin "SHIELD_1") (pinfunction "P$1_SHIELD_1") (pintype "bidirectional"))
    )
    (net (code "81") (name "unconnected-(X3-P$4-PadSHIELD_4)") (class "Default")
      (node (ref "X3") (pin "SHIELD_4") (pinfunction "P$4_SHIELD_4") (pintype "bidirectional"))
    )
  )
)
